# Sheet1.net
KiCad netlist of a schematic drawn in Altium Designer
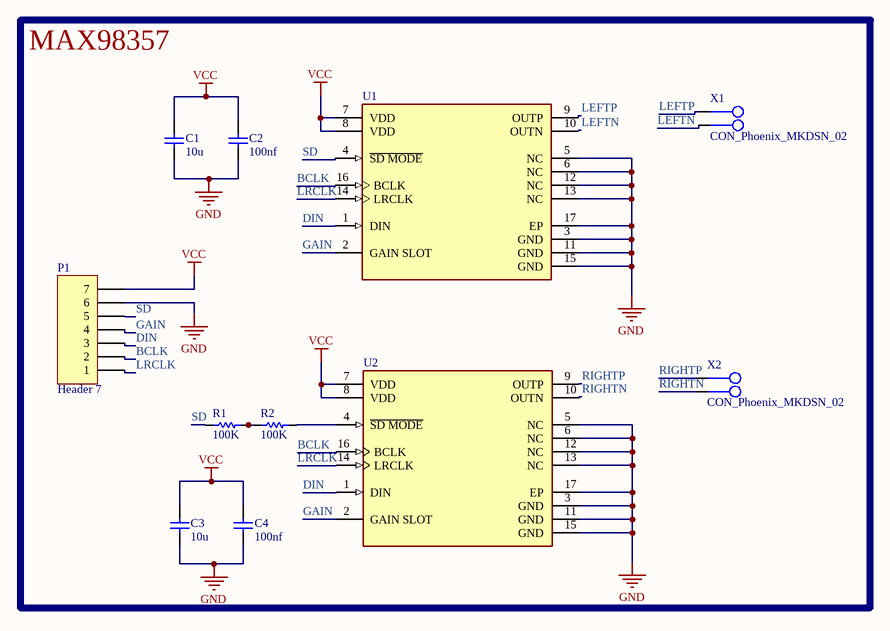
[diagram p0: Sheet1.SchDoc]

(export (version "E")
  (design (tool "Eeschema 10.0.6"))
  (components
    (comp (ref "C1")
      (value "10u")
      (footprint "CAP 0805")
      (description "Capacitor")
      (libsource (lib "AltiumLib1") (part "Capacitor"))
    )
    (comp (ref "C2")
      (value "100nf")
      (footprint "CAP 0805")
      (description "Capacitor")
      (libsource (lib "AltiumLib1") (part "Capacitor"))
    )
    (comp (ref "C3")
      (value "10u")
      (footprint "CAP 0805")
      (description "Capacitor")
      (libsource (lib "AltiumLib1") (part "Capacitor"))
    )
    (comp (ref "C4")
      (value "100nf")
      (footprint "CAP 0805")
      (description "Capacitor")
      (libsource (lib "AltiumLib1") (part "Capacitor"))
    )
    (comp (ref "P1")
      (value "Header 7")
      (footprint "HDR1X7")
      (description "Header, 7-Pin")
      (fields (field (name "PUBLISHER") "Altium Limited"))
      (libsource (lib "Altium") (part "Header 7"))
    )
    (comp (ref "R1")
      (value "100K")
      (footprint "RES 1206 (3216X08L)")
      (description "Resistor")
      (fields (field (name "TOLERANCE") "5%") (field (name "POWER") "1/4 W"))
      (libsource (lib "AltiumLib1") (part "Resistor"))
    )
    (comp (ref "R2")
      (value "100K")
      (footprint "RES 1206 (3216X08L)")
      (description "Resistor")
      (fields (field (name "TOLERANCE") "5%") (field (name "POWER") "1/4 W"))
      (libsource (lib "AltiumLib1") (part "Resistor"))
    )
    (comp (ref "U1")
      (value "~")
      (footprint "FP-T1633-4-IPC_A")
      (description "IC AMP CLASS D MONO 3.2W 16TQFN")
      (libsource (lib "MAX98357-16-TQFN") (part "CMP-05698-000018-1"))
    )
    (comp (ref "U2")
      (value "~")
      (footprint "FP-T1633-4-IPC_A")
      (description "IC AMP CLASS D MONO 3.2W 16TQFN")
      (libsource (lib "MAX98357-16-TQFN") (part "CMP-05698-000018-1"))
    )
    (comp (ref "X1")
      (value "CON_Phoenix_MKDSN_02")
      (footprint "CON_MKDSN1,5/2-5,08")
      (fields
        (field (name "MANUFACTURER") "PHOENIX CONTACT")
        (field (name "VOLTAGE") "400 V")
        (field (name "DESIGNER") "Eng. Saeid Jorablo")
        (field (name "PUBLISHER") "SJ UnLimited")
      )
      (libsource (lib "SJ Sockets & Connectors") (part "CON_Phoenix_MKDSN_02"))
    )
    (comp (ref "X2")
      (value "CON_Phoenix_MKDSN_02")
      (footprint "CON_MKDSN1,5/2-5,08")
      (fields
        (field (name "MANUFACTURER") "PHOENIX CONTACT")
        (field (name "VOLTAGE") "400 V")
        (field (name "DESIGNER") "Eng. Saeid Jorablo")
        (field (name "PUBLISHER") "SJ UnLimited")
      )
      (libsource (lib "SJ Sockets & Connectors") (part "CON_Phoenix_MKDSN_02"))
    )
  )
  (nets
    (net (code "1") (name "/BCLK") (class "Default")
      (node (ref "P1") (pin "2") (pinfunction "2_2") (pintype "passive"))
      (node (ref "U1") (pin "16") (pinfunction "BCLK_16") (pintype "input"))
      (node (ref "U2") (pin "16") (pinfunction "BCLK_16") (pintype "input"))
    )
    (net (code "2") (name "/DIN") (class "Default")
      (node (ref "P1") (pin "3") (pinfunction "3_3") (pintype "passive"))
      (node (ref "U1") (pin "1") (pinfunction "DIN_1") (pintype "input"))
      (node (ref "U2") (pin "1") (pinfunction "DIN_1") (pintype "input"))
    )
    (net (code "3") (name "/GAIN") (class "Default")
      (node (ref "P1") (pin "4") (pinfunction "4_4") (pintype "passive"))
      (node (ref "U1") (pin "2") (pinfunction "GAIN_SLOT_2") (pintype "passive"))
      (node (ref "U2") (pin "2") (pinfunction "GAIN_SLOT_2") (pintype "passive"))
    )
    (net (code "4") (name "/LEFTN") (class "Default")
      (node (ref "U1") (pin "10") (pinfunction "OUTN_10") (pintype "passive"))
      (node (ref "X1") (pin "2") (pinfunction "2_2") (pintype "passive"))
    )
    (net (code "5") (name "/LEFTP") (class "Default")
      (node (ref "U1") (pin "9") (pinfunction "OUTP_9") (pintype "passive"))
      (node (ref "X1") (pin "1") (pinfunction "1_1") (pintype "passive"))
    )
    (net (code "6") (name "/LRCLK") (class "Default")
      (node (ref "P1") (pin "1") (pinfunction "1_1") (pintype "passive"))
      (node (ref "U1") (pin "14") (pinfunction "LRCLK_14") (pintype "input"))
      (node (ref "U2") (pin "14") (pinfunction "LRCLK_14") (pintype "input"))
    )
    (net (code "7") (name "/RIGHTN") (class "Default")
      (node (ref "U2") (pin "10") (pinfunction "OUTN_10") (pintype "passive"))
      (node (ref "X2") (pin "2") (pinfunction "2_2") (pintype "passive"))
    )
    (net (code "8") (name "/RIGHTP") (class "Default")
      (node (ref "U2") (pin "9") (pinfunction "OUTP_9") (pintype "passive"))
      (node (ref "X2") (pin "1") (pinfunction "1_1") (pintype "passive"))
    )
    (net (code "9") (name "/SD") (class "Default")
      (node (ref "P1") (pin "5") (pinfunction "5_5") (pintype "passive"))
      (node (ref "R1") (pin "1") (pinfunction "1_1") (pintype "passive"))
      (node (ref "U1") (pin "4") (pinfunction "~{SD_MODE}_4") (pintype "input"))
    )
    (net (code "10") (name "GND") (class "Default")
      (node (ref "C1") (pin "2") (pinfunction "-_2") (pintype "passive"))
      (node (ref "C2") (pin "2") (pinfunction "-_2") (pintype "passive"))
      (node (ref "C3") (pin "2") (pinfunction "-_2") (pintype "passive"))
      (node (ref "C4") (pin "2") (pinfunction "-_2") (pintype "passive"))
      (node (ref "P1") (pin "6") (pinfunction "6_6") (pintype "passive"))
      (node (ref "U1") (pin "11") (pinfunction "GND_11") (pintype "power_in"))
      (node (ref "U1") (pin "12") (pinfunction "NC_12") (pintype "passive"))
      (node (ref "U1") (pin "13") (pinfunction "NC_13") (pintype "passive"))
      (node (ref "U1") (pin "15") (pinfunction "GND_15") (pintype "power_in"))
      (node (ref "U1") (pin "17") (pinfunction "EP_17") (pintype "passive"))
      (node (ref "U1") (pin "3") (pinfunction "GND_3") (pintype "power_in"))
      (node (ref "U1") (pin "5") (pinfunction "NC_5") (pintype "passive"))
      (node (ref "U1") (pin "6") (pinfunction "NC_6") (pintype "passive"))
      (node (ref "U2") (pin "11") (pinfunction "GND_11") (pintype "power_in"))
      (node (ref "U2") (pin "12") (pinfunction "NC_12") (pintype "passive"))
      (node (ref "U2") (pin "13") (pinfunction "NC_13") (pintype "passive"))
      (node (ref "U2") (pin "15") (pinfunction "GND_15") (pintype "power_in"))
      (node (ref "U2") (pin "17") (pinfunction "EP_17") (pintype "passive"))
      (node (ref "U2") (pin "3") (pinfunction "GND_3") (pintype "power_in"))
      (node (ref "U2") (pin "5") (pinfunction "NC_5") (pintype "passive"))
      (node (ref "U2") (pin "6") (pinfunction "NC_6") (pintype "passive"))
    )
    (net (code "11") (name "Net-(R1-Pad2)") (class "Default")
      (node (ref "R1") (pin "2") (pinfunction "2_2") (pintype "passive"))
      (node (ref "R2") (pin "1") (pinfunction "1_1") (pintype "passive"))
    )
    (net (code "12") (name "Net-(U2-~{SD_MODE})") (class "Default")
      (node (ref "R2") (pin "2") (pinfunction "2_2") (pintype "passive"))
      (node (ref "U2") (pin "4") (pinfunction "~{SD_MODE}_4") (pintype "input"))
    )
    (net (code "13") (name "VCC") (class "Default")
      (node (ref "C1") (pin "1") (pinfunction "+_1") (pintype "passive"))
      (node (ref "C2") (pin "1") (pinfunction "+_1") (pintype "passive"))
      (node (ref "C3") (pin "1") (pinfunction "+_1") (pintype "passive"))
      (node (ref "C4") (pin "1") (pinfunction "+_1") (pintype "passive"))
      (node (ref "P1") (pin "7") (pinfunction "7_7") (pintype "passive"))
      (node (ref "U1") (pin "7") (pinfunction "VDD_7") (pintype "power_in"))
      (node (ref "U1") (pin "8") (pinfunction "VDD_8") (pintype "power_in"))
      (node (ref "U2") (pin "7") (pinfunction "VDD_7") (pintype "power_in"))
      (node (ref "U2") (pin "8") (pinfunction "VDD_8") (pintype "power_in"))
    )
  )
)
